# ACC.net
KiCad netlist of a schematic drawn in EAGLE
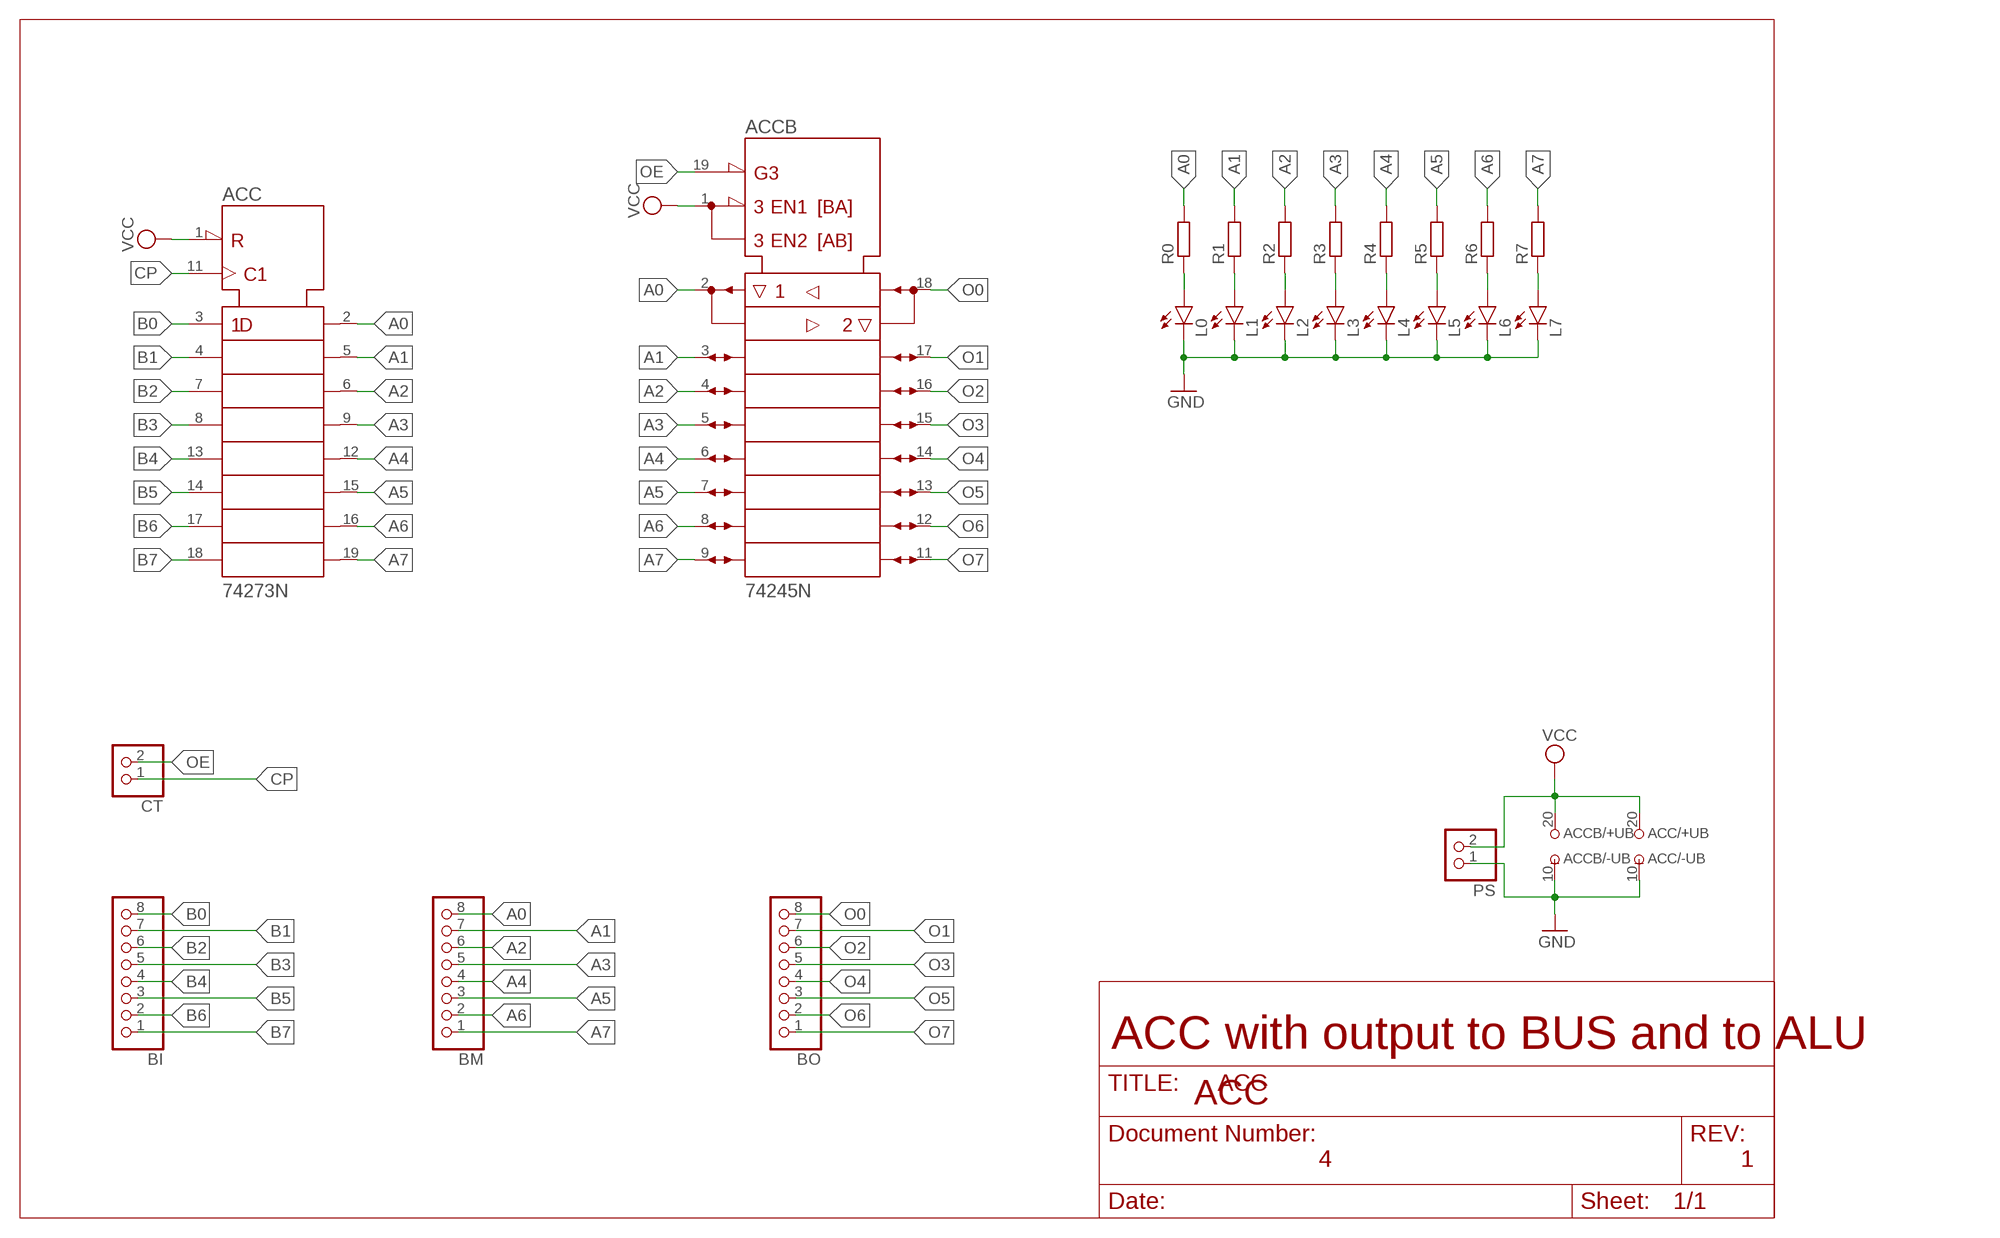
[diagram p0: schematic, sheet 1]

(export (version "E")
  (design (tool "Eeschema 10.0.6"))
  (components
    (comp (ref "ACC")
      (value "74273N")
      (footprint "eagle-import:DIL20")
      (libsource (lib "eagle-import") (part "74273N"))
    )
    (comp (ref "ACCB")
      (value "74245N")
      (footprint "eagle-import:DIL20")
      (libsource (lib "eagle-import") (part "74245N"))
    )
    (comp (ref "BI")
      (value "PINHD-1X8")
      (footprint "eagle-import:1X08")
      (libsource (lib "eagle-import") (part "PINHD-1X8"))
    )
    (comp (ref "BM")
      (value "PINHD-1X8")
      (footprint "eagle-import:1X08")
      (libsource (lib "eagle-import") (part "PINHD-1X8"))
    )
    (comp (ref "BO")
      (value "PINHD-1X8")
      (footprint "eagle-import:1X08")
      (libsource (lib "eagle-import") (part "PINHD-1X8"))
    )
    (comp (ref "CT")
      (value "PINHD-1X2")
      (footprint "eagle-import:1X02")
      (libsource (lib "eagle-import") (part "PINHD-1X2"))
    )
    (comp (ref "L0")
      (value "LED5MM")
      (footprint "eagle-import:LED5MM")
      (libsource (lib "eagle-import") (part "LED5MM"))
    )
    (comp (ref "L1")
      (value "LED5MM")
      (footprint "eagle-import:LED5MM")
      (libsource (lib "eagle-import") (part "LED5MM"))
    )
    (comp (ref "L2")
      (value "LED5MM")
      (footprint "eagle-import:LED5MM")
      (libsource (lib "eagle-import") (part "LED5MM"))
    )
    (comp (ref "L3")
      (value "LED5MM")
      (footprint "eagle-import:LED5MM")
      (libsource (lib "eagle-import") (part "LED5MM"))
    )
    (comp (ref "L4")
      (value "LED5MM")
      (footprint "eagle-import:LED5MM")
      (libsource (lib "eagle-import") (part "LED5MM"))
    )
    (comp (ref "L5")
      (value "LED5MM")
      (footprint "eagle-import:LED5MM")
      (libsource (lib "eagle-import") (part "LED5MM"))
    )
    (comp (ref "L6")
      (value "LED5MM")
      (footprint "eagle-import:LED5MM")
      (libsource (lib "eagle-import") (part "LED5MM"))
    )
    (comp (ref "L7")
      (value "LED5MM")
      (footprint "eagle-import:LED5MM")
      (libsource (lib "eagle-import") (part "LED5MM"))
    )
    (comp (ref "PS")
      (value "PINHD-1X2")
      (footprint "eagle-import:1X02")
      (libsource (lib "eagle-import") (part "PINHD-1X2"))
    )
    (comp (ref "R0")
      (value "R-EU_0204/7")
      (footprint "eagle-import:0204_7")
      (libsource (lib "eagle-import") (part "R-EU_0204/7"))
    )
    (comp (ref "R1")
      (value "R-EU_0204/7")
      (footprint "eagle-import:0204_7")
      (libsource (lib "eagle-import") (part "R-EU_0204/7"))
    )
    (comp (ref "R2")
      (value "R-EU_0204/7")
      (footprint "eagle-import:0204_7")
      (libsource (lib "eagle-import") (part "R-EU_0204/7"))
    )
    (comp (ref "R3")
      (value "R-EU_0204/7")
      (footprint "eagle-import:0204_7")
      (libsource (lib "eagle-import") (part "R-EU_0204/7"))
    )
    (comp (ref "R4")
      (value "R-EU_0204/7")
      (footprint "eagle-import:0204_7")
      (libsource (lib "eagle-import") (part "R-EU_0204/7"))
    )
    (comp (ref "R5")
      (value "R-EU_0204/7")
      (footprint "eagle-import:0204_7")
      (libsource (lib "eagle-import") (part "R-EU_0204/7"))
    )
    (comp (ref "R6")
      (value "R-EU_0204/7")
      (footprint "eagle-import:0204_7")
      (libsource (lib "eagle-import") (part "R-EU_0204/7"))
    )
    (comp (ref "R7")
      (value "R-EU_0204/7")
      (footprint "eagle-import:0204_7")
      (libsource (lib "eagle-import") (part "R-EU_0204/7"))
    )
  )
  (nets
    (net (code "1") (name "A0") (class "Default")
      (node (ref "ACC") (pin "2") (pinfunction "1Q_2") (pintype "output"))
      (node (ref "ACCB") (pin "2") (pinfunction "A1_2") (pintype "bidirectional"))
      (node (ref "BM") (pin "8") (pinfunction "8_8") (pintype "passive"))
      (node (ref "R0") (pin "2") (pinfunction "2_2") (pintype "passive"))
    )
    (net (code "2") (name "A1") (class "Default")
      (node (ref "ACC") (pin "5") (pinfunction "2Q_5") (pintype "output"))
      (node (ref "ACCB") (pin "3") (pinfunction "A2_3") (pintype "bidirectional"))
      (node (ref "BM") (pin "7") (pinfunction "7_7") (pintype "passive"))
      (node (ref "R1") (pin "2") (pinfunction "2_2") (pintype "passive"))
    )
    (net (code "3") (name "A2") (class "Default")
      (node (ref "ACC") (pin "6") (pinfunction "3Q_6") (pintype "output"))
      (node (ref "ACCB") (pin "4") (pinfunction "A3_4") (pintype "bidirectional"))
      (node (ref "BM") (pin "6") (pinfunction "6_6") (pintype "passive"))
      (node (ref "R2") (pin "2") (pinfunction "2_2") (pintype "passive"))
    )
    (net (code "4") (name "A3") (class "Default")
      (node (ref "ACC") (pin "9") (pinfunction "4Q_9") (pintype "output"))
      (node (ref "ACCB") (pin "5") (pinfunction "A4_5") (pintype "bidirectional"))
      (node (ref "BM") (pin "5") (pinfunction "5_5") (pintype "passive"))
      (node (ref "R3") (pin "2") (pinfunction "2_2") (pintype "passive"))
    )
    (net (code "5") (name "A4") (class "Default")
      (node (ref "ACC") (pin "12") (pinfunction "5Q_12") (pintype "output"))
      (node (ref "ACCB") (pin "6") (pinfunction "A5_6") (pintype "bidirectional"))
      (node (ref "BM") (pin "4") (pinfunction "4_4") (pintype "passive"))
      (node (ref "R4") (pin "2") (pinfunction "2_2") (pintype "passive"))
    )
    (net (code "6") (name "A5") (class "Default")
      (node (ref "ACC") (pin "15") (pinfunction "6Q_15") (pintype "output"))
      (node (ref "ACCB") (pin "7") (pinfunction "A6_7") (pintype "bidirectional"))
      (node (ref "BM") (pin "3") (pinfunction "3_3") (pintype "passive"))
      (node (ref "R5") (pin "2") (pinfunction "2_2") (pintype "passive"))
    )
    (net (code "7") (name "A6") (class "Default")
      (node (ref "ACC") (pin "16") (pinfunction "7Q_16") (pintype "output"))
      (node (ref "ACCB") (pin "8") (pinfunction "A7_8") (pintype "bidirectional"))
      (node (ref "BM") (pin "2") (pinfunction "2_2") (pintype "passive"))
      (node (ref "R6") (pin "2") (pinfunction "2_2") (pintype "passive"))
    )
    (net (code "8") (name "A7") (class "Default")
      (node (ref "ACC") (pin "19") (pinfunction "8Q_19") (pintype "output"))
      (node (ref "ACCB") (pin "9") (pinfunction "A8_9") (pintype "bidirectional"))
      (node (ref "BM") (pin "1") (pinfunction "1_1") (pintype "passive"))
      (node (ref "R7") (pin "2") (pinfunction "2_2") (pintype "passive"))
    )
    (net (code "9") (name "B0") (class "Default")
      (node (ref "ACC") (pin "3") (pinfunction "1D_3") (pintype "input"))
      (node (ref "BI") (pin "8") (pinfunction "8_8") (pintype "passive"))
    )
    (net (code "10") (name "B1") (class "Default")
      (node (ref "ACC") (pin "4") (pinfunction "2D_4") (pintype "input"))
      (node (ref "BI") (pin "7") (pinfunction "7_7") (pintype "passive"))
    )
    (net (code "11") (name "B2") (class "Default")
      (node (ref "ACC") (pin "7") (pinfunction "3D_7") (pintype "input"))
      (node (ref "BI") (pin "6") (pinfunction "6_6") (pintype "passive"))
    )
    (net (code "12") (name "B3") (class "Default")
      (node (ref "ACC") (pin "8") (pinfunction "4D_8") (pintype "input"))
      (node (ref "BI") (pin "5") (pinfunction "5_5") (pintype "passive"))
    )
    (net (code "13") (name "B4") (class "Default")
      (node (ref "ACC") (pin "13") (pinfunction "5D_13") (pintype "input"))
      (node (ref "BI") (pin "4") (pinfunction "4_4") (pintype "passive"))
    )
    (net (code "14") (name "B5") (class "Default")
      (node (ref "ACC") (pin "14") (pinfunction "6D_14") (pintype "input"))
      (node (ref "BI") (pin "3") (pinfunction "3_3") (pintype "passive"))
    )
    (net (code "15") (name "B6") (class "Default")
      (node (ref "ACC") (pin "17") (pinfunction "7D_17") (pintype "input"))
      (node (ref "BI") (pin "2") (pinfunction "2_2") (pintype "passive"))
    )
    (net (code "16") (name "B7") (class "Default")
      (node (ref "ACC") (pin "18") (pinfunction "8D_18") (pintype "input"))
      (node (ref "BI") (pin "1") (pinfunction "1_1") (pintype "passive"))
    )
    (net (code "17") (name "CP") (class "Default")
      (node (ref "ACC") (pin "11") (pinfunction "CLK_11") (pintype "input"))
      (node (ref "CT") (pin "1") (pinfunction "1_1") (pintype "passive"))
    )
    (net (code "18") (name "GND") (class "Default")
      (node (ref "ACC") (pin "10") (pinfunction "-UB_10") (pintype "power_in"))
      (node (ref "ACCB") (pin "10") (pinfunction "-UB_10") (pintype "power_in"))
      (node (ref "L0") (pin "K") (pinfunction "C_K") (pintype "passive"))
      (node (ref "L1") (pin "K") (pinfunction "C_K") (pintype "passive"))
      (node (ref "L2") (pin "K") (pinfunction "C_K") (pintype "passive"))
      (node (ref "L3") (pin "K") (pinfunction "C_K") (pintype "passive"))
      (node (ref "L4") (pin "K") (pinfunction "C_K") (pintype "passive"))
      (node (ref "L5") (pin "K") (pinfunction "C_K") (pintype "passive"))
      (node (ref "L6") (pin "K") (pinfunction "C_K") (pintype "passive"))
      (node (ref "L7") (pin "K") (pinfunction "C_K") (pintype "passive"))
      (node (ref "PS") (pin "1") (pinfunction "1_1") (pintype "passive"))
    )
    (net (code "19") (name "Net-(L0-PadA)") (class "Default")
      (node (ref "L0") (pin "A") (pinfunction "A_A") (pintype "passive"))
      (node (ref "R0") (pin "1") (pinfunction "1_1") (pintype "passive"))
    )
    (net (code "20") (name "Net-(L1-PadA)") (class "Default")
      (node (ref "L1") (pin "A") (pinfunction "A_A") (pintype "passive"))
      (node (ref "R1") (pin "1") (pinfunction "1_1") (pintype "passive"))
    )
    (net (code "21") (name "Net-(L2-PadA)") (class "Default")
      (node (ref "L2") (pin "A") (pinfunction "A_A") (pintype "passive"))
      (node (ref "R2") (pin "1") (pinfunction "1_1") (pintype "passive"))
    )
    (net (code "22") (name "Net-(L3-PadA)") (class "Default")
      (node (ref "L3") (pin "A") (pinfunction "A_A") (pintype "passive"))
      (node (ref "R3") (pin "1") (pinfunction "1_1") (pintype "passive"))
    )
    (net (code "23") (name "Net-(L4-PadA)") (class "Default")
      (node (ref "L4") (pin "A") (pinfunction "A_A") (pintype "passive"))
      (node (ref "R4") (pin "1") (pinfunction "1_1") (pintype "passive"))
    )
    (net (code "24") (name "Net-(L5-PadA)") (class "Default")
      (node (ref "L5") (pin "A") (pinfunction "A_A") (pintype "passive"))
      (node (ref "R5") (pin "1") (pinfunction "1_1") (pintype "passive"))
    )
    (net (code "25") (name "Net-(L6-PadA)") (class "Default")
      (node (ref "L6") (pin "A") (pinfunction "A_A") (pintype "passive"))
      (node (ref "R6") (pin "1") (pinfunction "1_1") (pintype "passive"))
    )
    (net (code "26") (name "Net-(L7-PadA)") (class "Default")
      (node (ref "L7") (pin "A") (pinfunction "A_A") (pintype "passive"))
      (node (ref "R7") (pin "1") (pinfunction "1_1") (pintype "passive"))
    )
    (net (code "27") (name "O0") (class "Default")
      (node (ref "ACCB") (pin "18") (pinfunction "B1_18") (pintype "bidirectional"))
      (node (ref "BO") (pin "8") (pinfunction "8_8") (pintype "passive"))
    )
    (net (code "28") (name "O1") (class "Default")
      (node (ref "ACCB") (pin "17") (pinfunction "B2_17") (pintype "bidirectional"))
      (node (ref "BO") (pin "7") (pinfunction "7_7") (pintype "passive"))
    )
    (net (code "29") (name "O2") (class "Default")
      (node (ref "ACCB") (pin "16") (pinfunction "B3_16") (pintype "bidirectional"))
      (node (ref "BO") (pin "6") (pinfunction "6_6") (pintype "passive"))
    )
    (net (code "30") (name "O3") (class "Default")
      (node (ref "ACCB") (pin "15") (pinfunction "B4_15") (pintype "bidirectional"))
      (node (ref "BO") (pin "5") (pinfunction "5_5") (pintype "passive"))
    )
    (net (code "31") (name "O4") (class "Default")
      (node (ref "ACCB") (pin "14") (pinfunction "B5_14") (pintype "bidirectional"))
      (node (ref "BO") (pin "4") (pinfunction "4_4") (pintype "passive"))
    )
    (net (code "32") (name "O5") (class "Default")
      (node (ref "ACCB") (pin "13") (pinfunction "B6_13") (pintype "bidirectional"))
      (node (ref "BO") (pin "3") (pinfunction "3_3") (pintype "passive"))
    )
    (net (code "33") (name "O6") (class "Default")
      (node (ref "ACCB") (pin "12") (pinfunction "B7_12") (pintype "bidirectional"))
      (node (ref "BO") (pin "2") (pinfunction "2_2") (pintype "passive"))
    )
    (net (code "34") (name "O7") (class "Default")
      (node (ref "ACCB") (pin "11") (pinfunction "B8_11") (pintype "bidirectional"))
      (node (ref "BO") (pin "1") (pinfunction "1_1") (pintype "passive"))
    )
    (net (code "35") (name "OE") (class "Default")
      (node (ref "ACCB") (pin "19") (pinfunction "~{G}_19") (pintype "input"))
      (node (ref "CT") (pin "2") (pinfunction "2_2") (pintype "passive"))
    )
    (net (code "36") (name "VCC") (class "Default")
      (node (ref "ACC") (pin "1") (pinfunction "~{CLR}_1") (pintype "input"))
      (node (ref "ACC") (pin "20") (pinfunction "+UB_20") (pintype "power_in"))
      (node (ref "ACCB") (pin "1") (pinfunction "DIR_1") (pintype "input"))
      (node (ref "ACCB") (pin "20") (pinfunction "+UB_20") (pintype "power_in"))
      (node (ref "PS") (pin "2") (pinfunction "2_2") (pintype "passive"))
    )
  )
)
